# GRHV_double_30v.net
KiCad netlist of a schematic drawn in Altium Designer
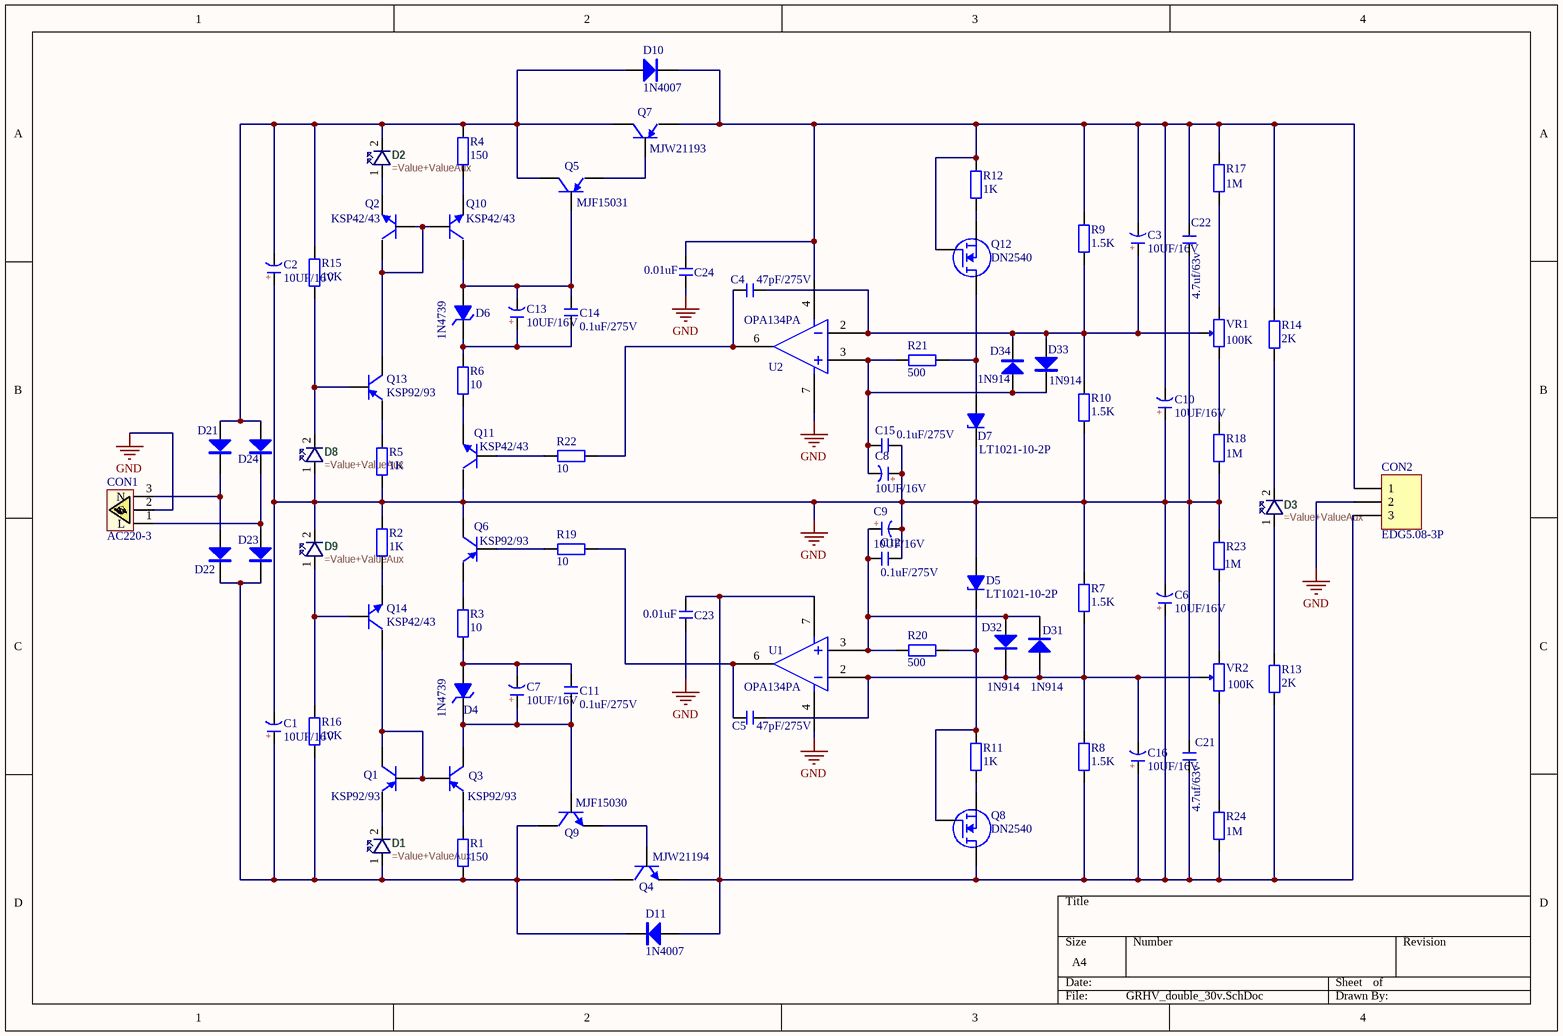
[diagram p0: GRHV_double_30v.SchDoc]

(export (version "E")
  (design (tool "Eeschema 10.0.6"))
  (components
    (comp (ref "C1")
      (value "10UF/16V")
      (footprint "CAP 1.5*4*8")
      (description "直插电解电容")
      (fields (field (name "版权归属") "源创客"))
      (libsource (lib "电阻-电容-电感") (part "C-CAP"))
    )
    (comp (ref "C2")
      (value "10UF/16V")
      (footprint "CAP 1.5*4*8")
      (description "直插电解电容")
      (fields (field (name "版权归属") "源创客"))
      (libsource (lib "电阻-电容-电感") (part "C-CAP"))
    )
    (comp (ref "C3")
      (value "10UF/16V")
      (footprint "CAP 1.5*4*8")
      (description "直插电解电容")
      (fields (field (name "版权归属") "源创客"))
      (libsource (lib "电阻-电容-电感") (part "C-CAP"))
    )
    (comp (ref "C4")
      (value "47pF/275V")
      (footprint "CBB 6.3*6.3*5")
      (description "CBB电容")
      (fields (field (name "版权归属") "源创客"))
      (libsource (lib "电阻-电容-电感") (part "C-CBB"))
    )
    (comp (ref "C5")
      (value "47pF/275V")
      (footprint "CBB 6.3*6.3*5")
      (description "CBB电容")
      (fields (field (name "版权归属") "源创客"))
      (libsource (lib "电阻-电容-电感") (part "C-CBB"))
    )
    (comp (ref "C6")
      (value "10UF/16V")
      (footprint "CAP 1.5*4*8")
      (description "直插电解电容")
      (fields (field (name "版权归属") "源创客"))
      (libsource (lib "电阻-电容-电感") (part "C-CAP"))
    )
    (comp (ref "C7")
      (value "10UF/16V")
      (footprint "CAP 1.5*4*8")
      (description "直插电解电容")
      (fields (field (name "版权归属") "源创客"))
      (libsource (lib "电阻-电容-电感") (part "C-CAP"))
    )
    (comp (ref "C8")
      (value "10UF/16V")
      (footprint "CAP 1.5*4*8")
      (description "直插电解电容")
      (fields (field (name "版权归属") "源创客"))
      (libsource (lib "") (part "C-CAP_1"))
    )
    (comp (ref "C9")
      (value "10UF/16V")
      (footprint "CAP 1.5*4*8")
      (description "直插电解电容")
      (fields (field (name "版权归属") "源创客"))
      (libsource (lib "") (part "C-CAP_1"))
    )
    (comp (ref "C10")
      (value "10UF/16V")
      (footprint "CAP 1.5*4*8")
      (description "直插电解电容")
      (fields (field (name "版权归属") "源创客"))
      (libsource (lib "电阻-电容-电感") (part "C-CAP"))
    )
    (comp (ref "C11")
      (value "0.1uF/275V")
      (footprint "CBB 6.3*6.3*5")
      (description "CBB电容")
      (fields (field (name "版权归属") "源创客"))
      (libsource (lib "电阻-电容-电感") (part "C-CBB"))
    )
    (comp (ref "C12")
      (value "0.1uF/275V")
      (footprint "CBB 6.3*6.3*5")
      (description "CBB电容")
      (fields (field (name "版权归属") "源创客"))
      (libsource (lib "电阻-电容-电感") (part "C-CBB"))
    )
    (comp (ref "C13")
      (value "10UF/16V")
      (footprint "CAP 1.5*4*8")
      (description "直插电解电容")
      (fields (field (name "版权归属") "源创客"))
      (libsource (lib "电阻-电容-电感") (part "C-CAP"))
    )
    (comp (ref "C14")
      (value "0.1uF/275V")
      (footprint "CBB 6.3*6.3*5")
      (description "CBB电容")
      (fields (field (name "版权归属") "源创客"))
      (libsource (lib "电阻-电容-电感") (part "C-CBB"))
    )
    (comp (ref "C15")
      (value "0.1uF/275V")
      (footprint "CBB 6.3*6.3*5")
      (description "CBB电容")
      (fields (field (name "版权归属") "源创客"))
      (libsource (lib "电阻-电容-电感") (part "C-CBB"))
    )
    (comp (ref "C16")
      (value "10UF/16V")
      (footprint "CAP 1.5*4*8")
      (description "直插电解电容")
      (fields (field (name "版权归属") "源创客"))
      (libsource (lib "电阻-电容-电感") (part "C-CAP"))
    )
    (comp (ref "C21")
      (value "4.7uf/63v")
      (footprint "CBB 7.2*7.2*13")
      (description "MKS薄膜电容")
      (libsource (lib "电阻-电容-电感") (part "C-MKS"))
    )
    (comp (ref "C22")
      (value "4.7uf/63v")
      (footprint "CBB 7.2*7.2*13")
      (description "MKS薄膜电容")
      (libsource (lib "电阻-电容-电感") (part "C-MKS"))
    )
    (comp (ref "C23")
      (value "0.01uF")
      (footprint "CBB 6.3*6.3*5")
      (description "CBB电容")
      (fields (field (name "Comment") "0.01uF/275V") (field (name "版权归属") "源创客"))
      (libsource (lib "电阻-电容-电感") (part "C-CBB"))
    )
    (comp (ref "C24")
      (value "0.01uF")
      (footprint "CBB 6.3*6.3*5")
      (description "CBB电容")
      (fields (field (name "Comment") "0.01uF/275V") (field (name "版权归属") "源创客"))
      (libsource (lib "电阻-电容-电感") (part "C-CBB"))
    )
    (comp (ref "CON1")
      (value "AC220-3")
      (footprint "HX5.08-3L")
      (libsource (lib "Connectors") (part "AC220-3"))
    )
    (comp (ref "CON2")
      (value "EDG5.08-3P")
      (footprint "HX5.08-3L")
      (libsource (lib "Connectors") (part "EDG5.08-3P"))
    )
    (comp (ref "D1")
      (value "~")
      (footprint "LED 3MM-R")
      (description "直插式LED")
      (libsource (lib "LED") (part "LED"))
    )
    (comp (ref "D2")
      (value "~")
      (footprint "LED 3MM-R")
      (description "直插式LED")
      (libsource (lib "LED") (part "LED"))
    )
    (comp (ref "D3")
      (value "~")
      (footprint "LED 3MM-R")
      (description "直插式LED")
      (libsource (lib "LED") (part "LED"))
    )
    (comp (ref "D4")
      (value "1N4739")
      (footprint "DO-41")
      (description "9.1V/1W稳压管")
      (libsource (lib "二极管-整流桥") (part "1N4739"))
    )
    (comp (ref "D5")
      (value "LT1021-10-2P")
      (footprint "DIP8-300_MH")
      (description "10V Precision Reference 2 Pin Config")
      (libsource (lib "电压参考") (part "LT1021-10-2P"))
    )
    (comp (ref "D6")
      (value "1N4739")
      (footprint "DO-41")
      (description "9.1V/1W稳压管")
      (libsource (lib "二极管-整流桥") (part "1N4739"))
    )
    (comp (ref "D7")
      (value "LT1021-10-2P")
      (footprint "DIP8-300_MH")
      (description "10V Precision Reference 2 Pin Config")
      (libsource (lib "电压参考") (part "LT1021-10-2P"))
    )
    (comp (ref "D8")
      (value "~")
      (footprint "LED 3MM-R")
      (description "直插式LED")
      (libsource (lib "LED") (part "LED"))
    )
    (comp (ref "D9")
      (value "~")
      (footprint "LED 3MM-R")
      (description "直插式LED")
      (libsource (lib "LED") (part "LED"))
    )
    (comp (ref "D10")
      (value "1N4007")
      (footprint "DO-41")
      (description "整流二极管")
      (fields (field (name "版权归属") "源创客"))
      (libsource (lib "二极管-整流桥") (part "1N4007"))
    )
    (comp (ref "D11")
      (value "1N4007")
      (footprint "DO-41")
      (description "整流二极管")
      (fields (field (name "版权归属") "源创客"))
      (libsource (lib "二极管-整流桥") (part "1N4007"))
    )
    (comp (ref "D21")
      (value "VS-HFA08TB60-M3")
      (footprint "TO220AC")
      (description "Ultrafast Soft Recovery Diado 8A 600V")
      (libsource (lib "二极管-整流桥") (part "VS-HFA08TB60-M3"))
    )
    (comp (ref "D22")
      (value "VS-HFA08TB60-M3")
      (footprint "TO220AC")
      (description "Ultrafast Soft Recovery Diado 8A 600V")
      (libsource (lib "二极管-整流桥") (part "VS-HFA08TB60-M3"))
    )
    (comp (ref "D23")
      (value "VS-HFA08TB60-M3")
      (footprint "TO220AC")
      (description "Ultrafast Soft Recovery Diado 8A 600V")
      (libsource (lib "二极管-整流桥") (part "VS-HFA08TB60-M3"))
    )
    (comp (ref "D24")
      (value "VS-HFA08TB60-M3")
      (footprint "TO220AC")
      (description "Ultrafast Soft Recovery Diado 8A 600V")
      (libsource (lib "二极管-整流桥") (part "VS-HFA08TB60-M3"))
    )
    (comp (ref "D31")
      (value "1N914")
      (footprint "DO-35")
      (description "高速开关管 1V/0.25W")
      (libsource (lib "二极管-整流桥") (part "1N914"))
    )
    (comp (ref "D32")
      (value "1N914")
      (footprint "DO-35")
      (description "高速开关管 1V/0.25W")
      (libsource (lib "二极管-整流桥") (part "1N914"))
    )
    (comp (ref "D33")
      (value "1N914")
      (footprint "DO-35")
      (description "高速开关管 1V/0.25W")
      (libsource (lib "二极管-整流桥") (part "1N914"))
    )
    (comp (ref "D34")
      (value "1N914")
      (footprint "DO-35")
      (description "高速开关管 1V/0.25W")
      (libsource (lib "二极管-整流桥") (part "1N914"))
    )
    (comp (ref "Q1")
      (value "KSP92/93")
      (footprint "TO92A")
      (description "High Voltage PNP Transistor")
      (libsource (lib "三极管") (part "KSP92/93"))
    )
    (comp (ref "Q2")
      (value "KSP42/43")
      (footprint "TO92A")
      (description "High Voltage NPN Transistor")
      (libsource (lib "三极管") (part "KSP42/43"))
    )
    (comp (ref "Q3")
      (value "KSP92/93")
      (footprint "TO92A")
      (description "High Voltage PNP Transistor")
      (libsource (lib "三极管") (part "KSP92/93"))
    )
    (comp (ref "Q4")
      (value "MJW21194")
      (footprint "TO247V")
      (description "Power NPN Transistor")
      (libsource (lib "三极管") (part "MJW21194"))
    )
    (comp (ref "Q5")
      (value "MJF15031")
      (footprint "TO220V")
      (description "Power PNP Transistor")
      (libsource (lib "三极管") (part "MJF15031"))
    )
    (comp (ref "Q6")
      (value "KSP92/93")
      (footprint "TO92A")
      (description "High Voltage PNP Transistor")
      (libsource (lib "三极管") (part "KSP92/93"))
    )
    (comp (ref "Q7")
      (value "MJW21193")
      (footprint "TO247V")
      (description "Power PNP Transistor")
      (libsource (lib "三极管") (part "MJW21193"))
    )
    (comp (ref "Q8")
      (value "DN2540")
      (footprint "TO92A")
      (description "N沟道耗尽型DMOS场效应管 400V/150ma")
      (libsource (lib "场效应管") (part "DN2540"))
    )
    (comp (ref "Q9")
      (value "MJF15030")
      (footprint "TO220V")
      (description "Power NPN Transistor")
      (libsource (lib "三极管") (part "MJF15030"))
    )
    (comp (ref "Q10")
      (value "KSP42/43")
      (footprint "TO92A")
      (description "High Voltage NPN Transistor")
      (libsource (lib "三极管") (part "KSP42/43"))
    )
    (comp (ref "Q11")
      (value "KSP42/43")
      (footprint "TO92A")
      (description "High Voltage NPN Transistor")
      (libsource (lib "三极管") (part "KSP42/43"))
    )
    (comp (ref "Q12")
      (value "DN2540")
      (footprint "TO92A")
      (description "N沟道耗尽型DMOS场效应管 400V/150ma")
      (libsource (lib "场效应管") (part "DN2540"))
    )
    (comp (ref "Q13")
      (value "KSP92/93")
      (footprint "TO92A")
      (description "High Voltage PNP Transistor")
      (libsource (lib "三极管") (part "KSP92/93"))
    )
    (comp (ref "Q14")
      (value "KSP42/43")
      (footprint "TO92A")
      (description "High Voltage NPN Transistor")
      (libsource (lib "三极管") (part "KSP42/43"))
    )
    (comp (ref "R1")
      (value "150")
      (footprint "RS 1/4W")
      (description "直插色环电阻")
      (fields (field (name "版权归属") "源创客"))
      (libsource (lib "电阻-电容-电感") (part "R-CRR"))
    )
    (comp (ref "R2")
      (value "1K")
      (footprint "RS 1/4W")
      (description "直插色环电阻")
      (fields (field (name "版权归属") "源创客"))
      (libsource (lib "电阻-电容-电感") (part "R-CRR"))
    )
    (comp (ref "R3")
      (value "10")
      (footprint "RS 1/4W")
      (description "直插色环电阻")
      (fields (field (name "版权归属") "源创客"))
      (libsource (lib "电阻-电容-电感") (part "R-CRR"))
    )
    (comp (ref "R4")
      (value "150")
      (footprint "RS 1/4W")
      (description "直插色环电阻")
      (fields (field (name "版权归属") "源创客"))
      (libsource (lib "电阻-电容-电感") (part "R-CRR"))
    )
    (comp (ref "R5")
      (value "1K")
      (footprint "RS 1/4W")
      (description "直插色环电阻")
      (fields (field (name "版权归属") "源创客"))
      (libsource (lib "电阻-电容-电感") (part "R-CRR"))
    )
    (comp (ref "R6")
      (value "10")
      (footprint "RS 1/4W")
      (description "直插色环电阻")
      (fields (field (name "版权归属") "源创客"))
      (libsource (lib "电阻-电容-电感") (part "R-CRR"))
    )
    (comp (ref "R7")
      (value "1.5K")
      (footprint "RS 1/4W")
      (description "直插色环电阻")
      (fields (field (name "版权归属") "源创客"))
      (libsource (lib "电阻-电容-电感") (part "R-CRR"))
    )
    (comp (ref "R8")
      (value "1.5K")
      (footprint "RS 1/4W")
      (description "直插色环电阻")
      (fields (field (name "版权归属") "源创客"))
      (libsource (lib "电阻-电容-电感") (part "R-CRR"))
    )
    (comp (ref "R9")
      (value "1.5K")
      (footprint "RS 1/4W")
      (description "直插色环电阻")
      (fields (field (name "版权归属") "源创客"))
      (libsource (lib "电阻-电容-电感") (part "R-CRR"))
    )
    (comp (ref "R10")
      (value "1.5K")
      (footprint "RS 1/4W")
      (description "直插色环电阻")
      (fields (field (name "版权归属") "源创客"))
      (libsource (lib "电阻-电容-电感") (part "R-CRR"))
    )
    (comp (ref "R11")
      (value "1K")
      (footprint "RS 1/4W")
      (description "直插色环电阻")
      (fields (field (name "版权归属") "源创客"))
      (libsource (lib "电阻-电容-电感") (part "R-CRR"))
    )
    (comp (ref "R12")
      (value "1K")
      (footprint "RS 1/4W")
      (description "直插色环电阻")
      (fields (field (name "版权归属") "源创客"))
      (libsource (lib "电阻-电容-电感") (part "R-CRR"))
    )
    (comp (ref "R13")
      (value "2K")
      (footprint "RS 1/4W")
      (description "直插色环电阻")
      (fields (field (name "版权归属") "源创客"))
      (libsource (lib "电阻-电容-电感") (part "R-CRR"))
    )
    (comp (ref "R14")
      (value "2K")
      (footprint "RS 1/4W")
      (description "直插色环电阻")
      (fields (field (name "版权归属") "源创客"))
      (libsource (lib "电阻-电容-电感") (part "R-CRR"))
    )
    (comp (ref "R15")
      (value "10K")
      (footprint "RS 1/4W")
      (description "直插色环电阻")
      (fields (field (name "版权归属") "源创客"))
      (libsource (lib "电阻-电容-电感") (part "R-CRR"))
    )
    (comp (ref "R16")
      (value "10K")
      (footprint "RS 1/4W")
      (description "直插色环电阻")
      (fields (field (name "版权归属") "源创客"))
      (libsource (lib "电阻-电容-电感") (part "R-CRR"))
    )
    (comp (ref "R17")
      (value "1M")
      (footprint "RS 1/4W")
      (description "直插色环电阻")
      (fields (field (name "版权归属") "源创客"))
      (libsource (lib "电阻-电容-电感") (part "R-CRR"))
    )
    (comp (ref "R18")
      (value "1M")
      (footprint "RS 1/4W")
      (description "直插色环电阻")
      (fields (field (name "版权归属") "源创客"))
      (libsource (lib "电阻-电容-电感") (part "R-CRR"))
    )
    (comp (ref "R19")
      (value "10")
      (footprint "RS 1/4W")
      (description "直插色环电阻")
      (fields (field (name "版权归属") "源创客"))
      (libsource (lib "电阻-电容-电感") (part "R-CRR"))
    )
    (comp (ref "R20")
      (value "500")
      (footprint "RS 1/4W")
      (description "直插色环电阻")
      (fields (field (name "版权归属") "源创客"))
      (libsource (lib "电阻-电容-电感") (part "R-CRR"))
    )
    (comp (ref "R21")
      (value "500")
      (footprint "RS 1/4W")
      (description "直插色环电阻")
      (fields (field (name "版权归属") "源创客"))
      (libsource (lib "电阻-电容-电感") (part "R-CRR"))
    )
    (comp (ref "R22")
      (value "10")
      (footprint "RS 1/4W")
      (description "直插色环电阻")
      (fields (field (name "版权归属") "源创客"))
      (libsource (lib "电阻-电容-电感") (part "R-CRR"))
    )
    (comp (ref "R23")
      (value "1M")
      (footprint "RS 1/4W")
      (description "直插色环电阻")
      (fields (field (name "版权归属") "源创客"))
      (libsource (lib "电阻-电容-电感") (part "R-CRR"))
    )
    (comp (ref "R24")
      (value "1M")
      (footprint "RS 1/4W")
      (description "直插色环电阻")
      (fields (field (name "版权归属") "源创客"))
      (libsource (lib "电阻-电容-电感") (part "R-CRR"))
    )
    (comp (ref "U1") (value "OPA134PA") (footprint "DIP8-300_MH") (libsource (lib "运放") (part "OPA134PA")))
    (comp (ref "U2") (value "OPA134PA") (footprint "DIP8-300_MH") (libsource (lib "运放") (part "OPA134PA")))
    (comp (ref "VR1")
      (value "100K")
      (footprint "RS 1/2W-VR")
      (description "直插可调电阻-顶调")
      (fields (field (name "Comment") "VR-W"))
      (libsource (lib "电阻-电容-电感") (part "VR-W"))
    )
    (comp (ref "VR2")
      (value "100K")
      (footprint "RS 1/2W-VR")
      (description "直插可调电阻-顶调")
      (fields (field (name "Comment") "VR-W"))
      (libsource (lib "电阻-电容-电感") (part "VR-W"))
    )
  )
  (nets
    (net (code "1") (name "GND") (class "Default")
      (node (ref "C1") (pin "2") (pinfunction "K_2") (pintype "passive"))
      (node (ref "C10") (pin "1") (pinfunction "A_1") (pintype "passive"))
      (node (ref "C12") (pin "2") (pinfunction "2_2") (pintype "passive"))
      (node (ref "C15") (pin "2") (pinfunction "2_2") (pintype "passive"))
      (node (ref "C2") (pin "1") (pinfunction "A_1") (pintype "passive"))
      (node (ref "C21") (pin "2") (pinfunction "2_2") (pintype "passive"))
      (node (ref "C22") (pin "1") (pinfunction "1_1") (pintype "passive"))
      (node (ref "C23") (pin "1") (pinfunction "1_1") (pintype "passive"))
      (node (ref "C24") (pin "1") (pinfunction "1_1") (pintype "passive"))
      (node (ref "C6") (pin "2") (pinfunction "K_2") (pintype "passive"))
      (node (ref "C8") (pin "1") (pinfunction "A_1") (pintype "passive"))
      (node (ref "C9") (pin "2") (pinfunction "K_2") (pintype "passive"))
      (node (ref "CON1") (pin "2") (pinfunction "G_2") (pintype "passive"))
      (node (ref "CON2") (pin "2") (pinfunction "2_2") (pintype "passive"))
      (node (ref "D5") (pin "4") (pinfunction "A_4") (pintype "passive"))
      (node (ref "D7") (pin "6") (pinfunction "K_6") (pintype "passive"))
      (node (ref "D8") (pin "1") (pinfunction "A_1") (pintype "passive"))
      (node (ref "D9") (pin "2") (pinfunction "K_2") (pintype "passive"))
      (node (ref "Q11") (pin "3") (pinfunction "C_3") (pintype "passive"))
      (node (ref "Q6") (pin "3") (pinfunction "C_3") (pintype "passive"))
      (node (ref "R10") (pin "1") (pinfunction "1_1") (pintype "passive"))
      (node (ref "R18") (pin "1") (pinfunction "1_1") (pintype "passive"))
      (node (ref "R2") (pin "2") (pinfunction "2_2") (pintype "passive"))
      (node (ref "R23") (pin "2") (pinfunction "2_2") (pintype "passive"))
      (node (ref "R5") (pin "1") (pinfunction "1_1") (pintype "passive"))
      (node (ref "R7") (pin "2") (pinfunction "2_2") (pintype "passive"))
      (node (ref "U1") (pin "4") (pinfunction "V-_4") (pintype "passive"))
      (node (ref "U2") (pin "7") (pinfunction "V+_7") (pintype "passive"))
    )
    (net (code "2") (name "Net-(C1-A)") (class "Default")
      (node (ref "C1") (pin "1") (pinfunction "A_1") (pintype "passive"))
      (node (ref "D1") (pin "1") (pinfunction "A_1") (pintype "passive"))
      (node (ref "D11") (pin "2") (pinfunction "K_2") (pintype "passive"))
      (node (ref "D22") (pin "1") (pinfunction "Cathode_1") (pintype "passive"))
      (node (ref "D23") (pin "1") (pinfunction "Cathode_1") (pintype "passive"))
      (node (ref "Q4") (pin "2") (pinfunction "C_2") (pintype "passive"))
      (node (ref "Q9") (pin "2") (pinfunction "C_2") (pintype "passive"))
      (node (ref "R1") (pin "1") (pinfunction "1_1") (pintype "passive"))
      (node (ref "R16") (pin "1") (pinfunction "1_1") (pintype "passive"))
    )
    (net (code "3") (name "Net-(C2-K)") (class "Default")
      (node (ref "C2") (pin "2") (pinfunction "K_2") (pintype "passive"))
      (node (ref "D10") (pin "1") (pinfunction "A_1") (pintype "passive"))
      (node (ref "D2") (pin "2") (pinfunction "K_2") (pintype "passive"))
      (node (ref "D21") (pin "2") (pinfunction "Anode_2") (pintype "passive"))
      (node (ref "D24") (pin "2") (pinfunction "Anode_2") (pintype "passive"))
      (node (ref "Q5") (pin "2") (pinfunction "C_2") (pintype "passive"))
      (node (ref "Q7") (pin "2") (pinfunction "C_2") (pintype "passive"))
      (node (ref "R15") (pin "2") (pinfunction "2_2") (pintype "passive"))
      (node (ref "R4") (pin "2") (pinfunction "2_2") (pintype "passive"))
    )
    (net (code "4") (name "Net-(C3-A)") (class "Default")
      (node (ref "C3") (pin "1") (pinfunction "A_1") (pintype "passive"))
      (node (ref "C4") (pin "2") (pinfunction "2_2") (pintype "passive"))
      (node (ref "D33") (pin "1") (pinfunction "A_1") (pintype "passive"))
      (node (ref "D34") (pin "2") (pinfunction "K_2") (pintype "passive"))
      (node (ref "R10") (pin "2") (pinfunction "2_2") (pintype "passive"))
      (node (ref "R9") (pin "1") (pinfunction "1_1") (pintype "passive"))
      (node (ref "U2") (pin "2") (pinfunction "-in_2") (pintype "passive"))
      (node (ref "VR1") (pin "3") (pinfunction "3_3") (pintype "passive"))
    )
    (net (code "5") (name "Net-(C7-A)") (class "Default")
      (node (ref "C11") (pin "1") (pinfunction "1_1") (pintype "passive"))
      (node (ref "C7") (pin "1") (pinfunction "A_1") (pintype "passive"))
      (node (ref "D4") (pin "2") (pinfunction "K_2") (pintype "passive"))
      (node (ref "Q3") (pin "3") (pinfunction "C_3") (pintype "passive"))
      (node (ref "Q9") (pin "1") (pinfunction "B_1") (pintype "passive"))
    )
    (net (code "6") (name "Net-(C7-K)") (class "Default")
      (node (ref "C11") (pin "2") (pinfunction "2_2") (pintype "passive"))
      (node (ref "C7") (pin "2") (pinfunction "K_2") (pintype "passive"))
      (node (ref "D4") (pin "1") (pinfunction "A_1") (pintype "passive"))
      (node (ref "R3") (pin "1") (pinfunction "1_1") (pintype "passive"))
    )
    (net (code "7") (name "Net-(C8-K)") (class "Default")
      (node (ref "C15") (pin "1") (pinfunction "1_1") (pintype "passive"))
      (node (ref "C8") (pin "2") (pinfunction "K_2") (pintype "passive"))
      (node (ref "D33") (pin "2") (pinfunction "K_2") (pintype "passive"))
      (node (ref "D34") (pin "1") (pinfunction "A_1") (pintype "passive"))
      (node (ref "R21") (pin "1") (pinfunction "1_1") (pintype "passive"))
      (node (ref "U2") (pin "3") (pinfunction "+in_3") (pintype "passive"))
    )
    (net (code "8") (name "Net-(C9-A)") (class "Default")
      (node (ref "C12") (pin "1") (pinfunction "1_1") (pintype "passive"))
      (node (ref "C9") (pin "1") (pinfunction "A_1") (pintype "passive"))
      (node (ref "D31") (pin "2") (pinfunction "K_2") (pintype "passive"))
      (node (ref "D32") (pin "1") (pinfunction "A_1") (pintype "passive"))
      (node (ref "R20") (pin "1") (pinfunction "1_1") (pintype "passive"))
      (node (ref "U1") (pin "3") (pinfunction "+in_3") (pintype "passive"))
    )
    (net (code "9") (name "Net-(C10-K)") (class "Default")
      (node (ref "C10") (pin "2") (pinfunction "K_2") (pintype "passive"))
      (node (ref "C22") (pin "2") (pinfunction "2_2") (pintype "passive"))
      (node (ref "C24") (pin "2") (pinfunction "2_2") (pintype "passive"))
      (node (ref "C3") (pin "2") (pinfunction "K_2") (pintype "passive"))
      (node (ref "CON2") (pin "1") (pinfunction "1_1") (pintype "passive"))
      (node (ref "D10") (pin "2") (pinfunction "K_2") (pintype "passive"))
      (node (ref "Q12") (pin "2") (pinfunction "G_2") (pintype "passive"))
      (node (ref "Q7") (pin "3") (pinfunction "E_3") (pintype "passive"))
      (node (ref "R12") (pin "2") (pinfunction "2_2") (pintype "passive"))
      (node (ref "R14") (pin "2") (pinfunction "2_2") (pintype "passive"))
      (node (ref "R17") (pin "2") (pinfunction "2_2") (pintype "passive"))
      (node (ref "R9") (pin "2") (pinfunction "2_2") (pintype "passive"))
      (node (ref "U2") (pin "4") (pinfunction "V-_4") (pintype "passive"))
    )
    (net (code "10") (name "Net-(C13-A)") (class "Default")
      (node (ref "C13") (pin "1") (pinfunction "A_1") (pintype "passive"))
      (node (ref "C14") (pin "1") (pinfunction "1_1") (pintype "passive"))
      (node (ref "D6") (pin "2") (pinfunction "K_2") (pintype "passive"))
      (node (ref "R6") (pin "2") (pinfunction "2_2") (pintype "passive"))
    )
    (net (code "11") (name "Net-(C13-K)") (class "Default")
      (node (ref "C13") (pin "2") (pinfunction "K_2") (pintype "passive"))
      (node (ref "C14") (pin "2") (pinfunction "2_2") (pintype "passive"))
      (node (ref "D6") (pin "1") (pinfunction "A_1") (pintype "passive"))
      (node (ref "Q10") (pin "3") (pinfunction "C_3") (pintype "passive"))
      (node (ref "Q5") (pin "1") (pinfunction "B_1") (pintype "passive"))
    )
    (net (code "12") (name "Net-(C16-A)") (class "Default")
      (node (ref "C16") (pin "1") (pinfunction "A_1") (pintype "passive"))
      (node (ref "C21") (pin "1") (pinfunction "1_1") (pintype "passive"))
      (node (ref "C23") (pin "2") (pinfunction "2_2") (pintype "passive"))
      (node (ref "C6") (pin "1") (pinfunction "A_1") (pintype "passive"))
      (node (ref "CON2") (pin "3") (pinfunction "3_3") (pintype "passive"))
      (node (ref "D11") (pin "1") (pinfunction "A_1") (pintype "passive"))
      (node (ref "Q4") (pin "3") (pinfunction "E_3") (pintype "passive"))
      (node (ref "Q8") (pin "3") (pinfunction "D_3") (pintype "passive"))
      (node (ref "R13") (pin "2") (pinfunction "2_2") (pintype "passive"))
      (node (ref "R24") (pin "1") (pinfunction "1_1") (pintype "passive"))
      (node (ref "R8") (pin "1") (pinfunction "1_1") (pintype "passive"))
      (node (ref "U1") (pin "7") (pinfunction "V+_7") (pintype "passive"))
    )
    (net (code "13") (name "Net-(C16-K)") (class "Default")
      (node (ref "C16") (pin "2") (pinfunction "K_2") (pintype "passive"))
      (node (ref "C5") (pin "2") (pinfunction "2_2") (pintype "passive"))
      (node (ref "D31") (pin "1") (pinfunction "A_1") (pintype "passive"))
      (node (ref "D32") (pin "2") (pinfunction "K_2") (pintype "passive"))
      (node (ref "R7") (pin "1") (pinfunction "1_1") (pintype "passive"))
      (node (ref "R8") (pin "2") (pinfunction "2_2") (pintype "passive"))
      (node (ref "U1") (pin "2") (pinfunction "-in_2") (pintype "passive"))
      (node (ref "VR2") (pin "3") (pinfunction "3_3") (pintype "passive"))
    )
    (net (code "14") (name "Net-(CON1-L)") (class "Default")
      (node (ref "CON1") (pin "1") (pinfunction "L_1") (pintype "passive"))
      (node (ref "D23") (pin "2") (pinfunction "Anode_2") (pintype "passive"))
      (node (ref "D24") (pin "1") (pinfunction "Cathode_1") (pintype "passive"))
    )
    (net (code "15") (name "Net-(CON1-N)") (class "Default")
      (node (ref "CON1") (pin "3") (pinfunction "N_3") (pintype "passive"))
      (node (ref "D21") (pin "1") (pinfunction "Cathode_1") (pintype "passive"))
      (node (ref "D22") (pin "2") (pinfunction "Anode_2") (pintype "passive"))
    )
    (net (code "16") (name "Net-(D1-K)") (class "Default")
      (node (ref "D1") (pin "2") (pinfunction "K_2") (pintype "passive"))
      (node (ref "Q1") (pin "1") (pinfunction "E_1") (pintype "passive"))
    )
    (net (code "17") (name "Net-(D2-A)") (class "Default")
      (node (ref "D2") (pin "1") (pinfunction "A_1") (pintype "passive"))
      (node (ref "Q2") (pin "1") (pinfunction "E_1") (pintype "passive"))
    )
    (net (code "18") (name "Net-(D3-A)") (class "Default")
      (node (ref "D3") (pin "1") (pinfunction "A_1") (pintype "passive"))
      (node (ref "R13") (pin "1") (pinfunction "1_1") (pintype "passive"))
    )
    (net (code "19") (name "Net-(D3-K)") (class "Default")
      (node (ref "D3") (pin "2") (pinfunction "K_2") (pintype "passive"))
      (node (ref "R14") (pin "1") (pinfunction "1_1") (pintype "passive"))
    )
    (net (code "20") (name "Net-(D5-K)") (class "Default")
      (node (ref "D5") (pin "6") (pinfunction "K_6") (pintype "passive"))
      (node (ref "Q8") (pin "2") (pinfunction "G_2") (pintype "passive"))
      (node (ref "R11") (pin "2") (pinfunction "2_2") (pintype "passive"))
      (node (ref "R20") (pin "2") (pinfunction "2_2") (pintype "passive"))
    )
    (net (code "21") (name "Net-(D7-A)") (class "Default")
      (node (ref "D7") (pin "4") (pinfunction "A_4") (pintype "passive"))
      (node (ref "Q12") (pin "3") (pinfunction "D_3") (pintype "passive"))
      (node (ref "R21") (pin "2") (pinfunction "2_2") (pintype "passive"))
    )
    (net (code "22") (name "Net-(D8-K)") (class "Default")
      (node (ref "D8") (pin "2") (pinfunction "K_2") (pintype "passive"))
      (node (ref "Q13") (pin "2") (pinfunction "B_2") (pintype "passive"))
      (node (ref "R15") (pin "1") (pinfunction "1_1") (pintype "passive"))
    )
    (net (code "23") (name "Net-(D9-A)") (class "Default")
      (node (ref "D9") (pin "1") (pinfunction "A_1") (pintype "passive"))
      (node (ref "Q14") (pin "2") (pinfunction "B_2") (pintype "passive"))
      (node (ref "R16") (pin "2") (pinfunction "2_2") (pintype "passive"))
    )
    (net (code "24") (name "Net-(Q1-B)") (class "Default")
      (node (ref "Q1") (pin "2") (pinfunction "B_2") (pintype "passive"))
      (node (ref "Q1") (pin "3") (pinfunction "C_3") (pintype "passive"))
      (node (ref "Q14") (pin "3") (pinfunction "C_3") (pintype "passive"))
      (node (ref "Q3") (pin "2") (pinfunction "B_2") (pintype "passive"))
    )
    (net (code "25") (name "Net-(Q3-E)") (class "Default")
      (node (ref "Q3") (pin "1") (pinfunction "E_1") (pintype "passive"))
      (node (ref "R1") (pin "2") (pinfunction "2_2") (pintype "passive"))
    )
    (net (code "26") (name "Net-(Q4-B)") (class "Default")
      (node (ref "Q4") (pin "1") (pinfunction "B_1") (pintype "passive"))
      (node (ref "Q9") (pin "3") (pinfunction "E_3") (pintype "passive"))
    )
    (net (code "27") (name "Net-(Q5-E)") (class "Default")
      (node (ref "Q5") (pin "3") (pinfunction "E_3") (pintype "passive"))
      (node (ref "Q7") (pin "1") (pinfunction "B_1") (pintype "passive"))
    )
    (net (code "28") (name "Net-(Q6-B)") (class "Default")
      (node (ref "Q6") (pin "2") (pinfunction "B_2") (pintype "passive"))
      (node (ref "R19") (pin "1") (pinfunction "1_1") (pintype "passive"))
    )
    (net (code "29") (name "Net-(Q6-E)") (class "Default")
      (node (ref "Q6") (pin "1") (pinfunction "E_1") (pintype "passive"))
      (node (ref "R3") (pin "2") (pinfunction "2_2") (pintype "passive"))
    )
    (net (code "30") (name "Net-(Q8-S)") (class "Default")
      (node (ref "Q8") (pin "1") (pinfunction "S_1") (pintype "passive"))
      (node (ref "R11") (pin "1") (pinfunction "1_1") (pintype "passive"))
    )
    (net (code "31") (name "Net-(Q10-B)") (class "Default")
      (node (ref "Q10") (pin "2") (pinfunction "B_2") (pintype "passive"))
      (node (ref "Q13") (pin "3") (pinfunction "C_3") (pintype "passive"))
      (node (ref "Q2") (pin "2") (pinfunction "B_2") (pintype "passive"))
      (node (ref "Q2") (pin "3") (pinfunction "C_3") (pintype "passive"))
    )
    (net (code "32") (name "Net-(Q10-E)") (class "Default")
      (node (ref "Q10") (pin "1") (pinfunction "E_1") (pintype "passive"))
      (node (ref "R4") (pin "1") (pinfunction "1_1") (pintype "passive"))
    )
    (net (code "33") (name "Net-(Q11-B)") (class "Default")
      (node (ref "Q11") (pin "2") (pinfunction "B_2") (pintype "passive"))
      (node (ref "R22") (pin "1") (pinfunction "1_1") (pintype "passive"))
    )
    (net (code "34") (name "Net-(Q11-E)") (class "Default")
      (node (ref "Q11") (pin "1") (pinfunction "E_1") (pintype "passive"))
      (node (ref "R6") (pin "1") (pinfunction "1_1") (pintype "passive"))
    )
    (net (code "35") (name "Net-(Q12-S)") (class "Default")
      (node (ref "Q12") (pin "1") (pinfunction "S_1") (pintype "passive"))
      (node (ref "R12") (pin "1") (pinfunction "1_1") (pintype "passive"))
    )
    (net (code "36") (name "Net-(Q13-E)") (class "Default")
      (node (ref "Q13") (pin "1") (pinfunction "E_1") (pintype "passive"))
      (node (ref "R5") (pin "2") (pinfunction "2_2") (pintype "passive"))
    )
    (net (code "37") (name "Net-(Q14-E)") (class "Default")
      (node (ref "Q14") (pin "1") (pinfunction "E_1") (pintype "passive"))
      (node (ref "R2") (pin "1") (pinfunction "1_1") (pintype "passive"))
    )
    (net (code "38") (name "Net-(R17-Pad1)") (class "Default")
      (node (ref "R17") (pin "1") (pinfunction "1_1") (pintype "passive"))
      (node (ref "VR1") (pin "2") (pinfunction "2_2") (pintype "passive"))
    )
    (net (code "39") (name "Net-(R18-Pad2)") (class "Default")
      (node (ref "R18") (pin "2") (pinfunction "2_2") (pintype "passive"))
      (node (ref "VR1") (pin "1") (pinfunction "1_1") (pintype "passive"))
    )
    (net (code "40") (name "Net-(R23-Pad1)") (class "Default")
      (node (ref "R23") (pin "1") (pinfunction "1_1") (pintype "passive"))
      (node (ref "VR2") (pin "2") (pinfunction "2_2") (pintype "passive"))
    )
    (net (code "41") (name "Net-(R24-Pad2)") (class "Default")
      (node (ref "R24") (pin "2") (pinfunction "2_2") (pintype "passive"))
      (node (ref "VR2") (pin "1") (pinfunction "1_1") (pintype "passive"))
    )
    (net (code "42") (name "Net-(U1-out)") (class "Default")
      (node (ref "C5") (pin "1") (pinfunction "1_1") (pintype "passive"))
      (node (ref "R19") (pin "2") (pinfunction "2_2") (pintype "passive"))
      (node (ref "U1") (pin "6") (pinfunction "out_6") (pintype "passive"))
    )
    (net (code "43") (name "Net-(U2-out)") (class "Default")
      (node (ref "C4") (pin "1") (pinfunction "1_1") (pintype "passive"))
      (node (ref "R22") (pin "2") (pinfunction "2_2") (pintype "passive"))
      (node (ref "U2") (pin "6") (pinfunction "out_6") (pintype "passive"))
    )
  )
)
